# Colour-Sensor.net
KiCad netlist of a schematic drawn in Altium Designer
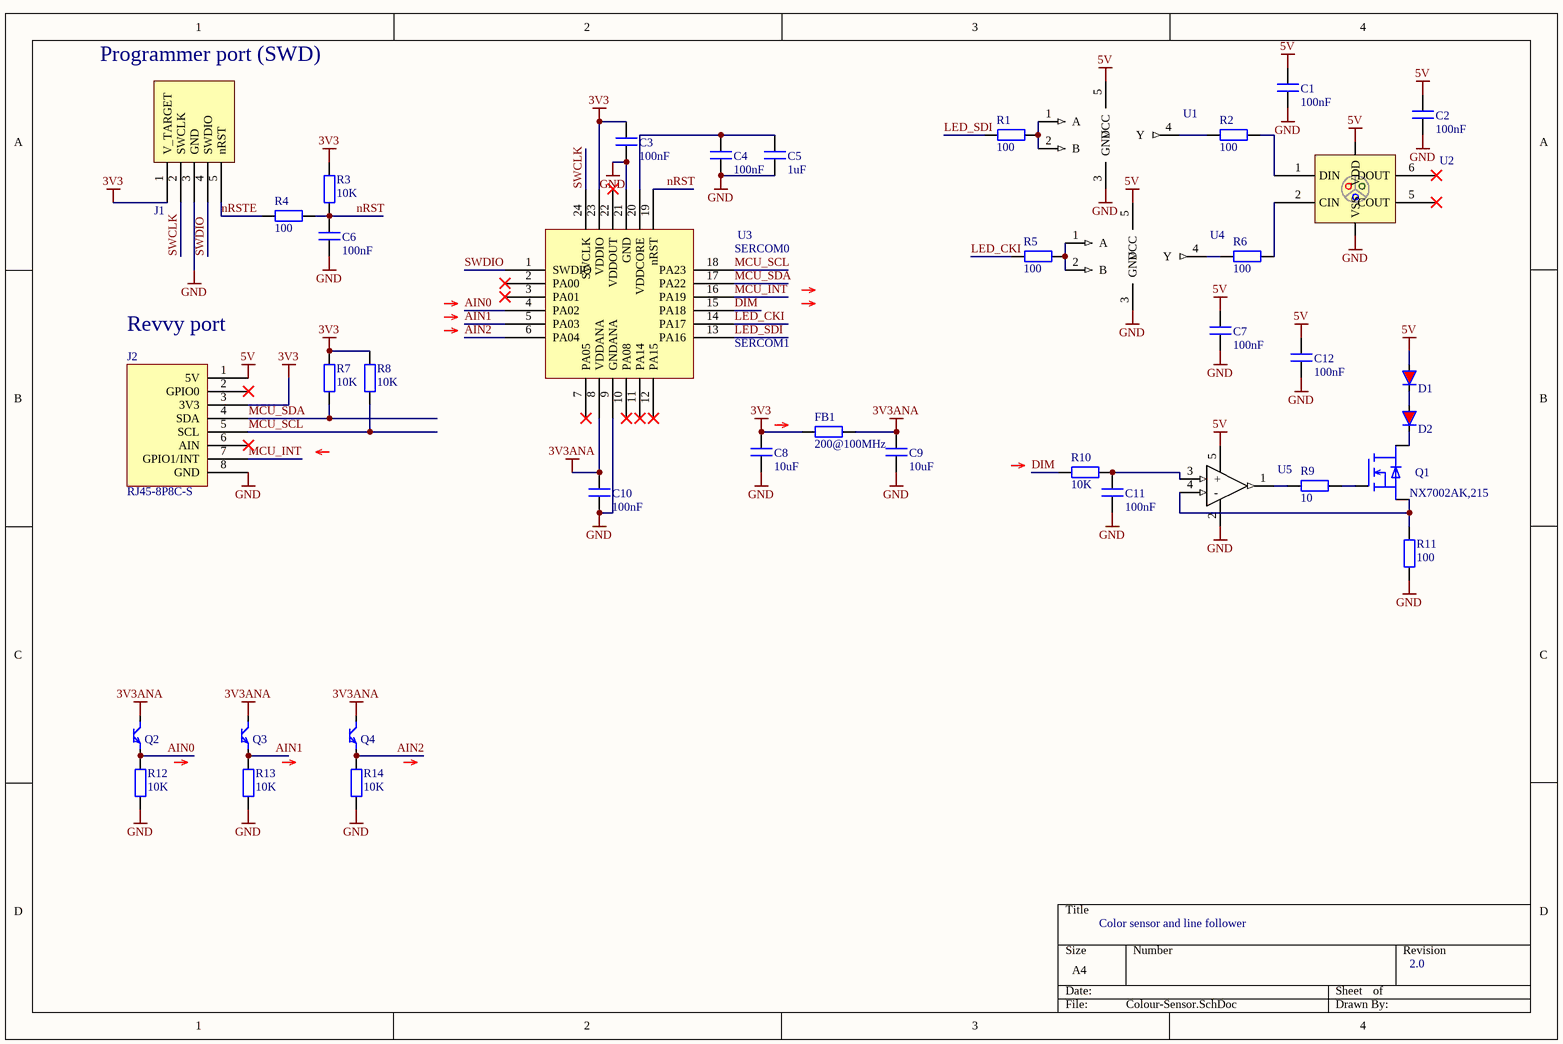
[diagram p0: Colour-Sensor.SchDoc]

(export (version "E")
  (design (tool "Eeschema 10.0.6"))
  (components
    (comp (ref "C1")
      (value "100nF")
      (footprint "CAP1608X06M")
      (libsource (lib "ColorSensor") (part "Capacitor 100n"))
    )
    (comp (ref "C2")
      (value "100nF")
      (footprint "CAP1608X06M")
      (libsource (lib "ColorSensor") (part "Capacitor 100n"))
    )
    (comp (ref "C3")
      (value "100nF")
      (footprint "CAP1608X06M")
      (libsource (lib "ColorSensor") (part "Capacitor 100n"))
    )
    (comp (ref "C4")
      (value "100nF")
      (footprint "CAP1608X06M")
      (libsource (lib "ColorSensor") (part "Capacitor 100n"))
    )
    (comp (ref "C5")
      (value "1uF")
      (footprint "CAP1608X06M")
      (libsource (lib "ColorSensor") (part "Capacitor 1u"))
    )
    (comp (ref "C6")
      (value "100nF")
      (footprint "CAP1608X06M")
      (libsource (lib "ColorSensor") (part "Capacitor 100n"))
    )
    (comp (ref "C7")
      (value "100nF")
      (footprint "CAP1608X06M")
      (libsource (lib "ColorSensor") (part "Capacitor 100n"))
    )
    (comp (ref "C8")
      (value "10uF")
      (footprint "CAP1608X06M")
      (libsource (lib "ColorSensor") (part "Capacitor 10u"))
    )
    (comp (ref "C9")
      (value "10uF")
      (footprint "CAP1608X06M")
      (libsource (lib "ColorSensor") (part "Capacitor 10u"))
    )
    (comp (ref "C10")
      (value "100nF")
      (footprint "CAP1608X06M")
      (libsource (lib "ColorSensor") (part "Capacitor 100n"))
    )
    (comp (ref "C11")
      (value "100nF")
      (footprint "CAP1608X06M")
      (libsource (lib "ColorSensor") (part "Capacitor 100n"))
    )
    (comp (ref "C12")
      (value "100nF")
      (footprint "CAP1608X06M")
      (libsource (lib "ColorSensor") (part "Capacitor 100n"))
    )
    (comp (ref "D1")
      (value "LTST-C190CKT")
      (footprint "SamacSys:LEDC1608X90N")
      (description "LED")
      (fields (field (name "MOUSER2 PART NUMBER") "859-LTST-C190CKT"))
      (libsource (lib "ColorSensor") (part "LTST-C190CKT"))
    )
    (comp (ref "D2")
      (value "LTST-C190CKT")
      (footprint "SamacSys:LEDC1608X90N")
      (description "LED")
      (fields (field (name "MOUSER2 PART NUMBER") "859-LTST-C190CKT"))
      (libsource (lib "ColorSensor") (part "LTST-C190CKT"))
    )
    (comp (ref "FB1")
      (value "200@100MHz")
      (footprint "RESC1608X06M")
      (libsource (lib "ColorSensor") (part "Generic ferrite bead"))
    )
    (comp (ref "J1")
      (value "SWD")
      (footprint "Sullins_GRPB051VWVN-RC")
      (libsource (lib "ColorSensor") (part "SWD"))
    )
    (comp (ref "J2")
      (value "RJ45-8P8C-S")
      (footprint "RJ45-8P8C")
      (libsource (lib "ColorSensor") (part "RJ45-8P8C-S"))
    )
    (comp (ref "Q1")
      (value "NX7002AK,215")
      (footprint "SOT-23-3")
      (fields (field (name "MANUFACTURER") "Nexperia") (field (name "AUTHOR") "ChAl"))
      (libsource (lib "ColorSensor") (part "NX7002AK,215"))
    )
    (comp (ref "Q2")
      (value "KDT00030TR")
      (footprint "SamacSys:KDT00030TR")
      (description "Phototransistor")
      (libsource (lib "ColorSensor") (part "KDT00030TR"))
    )
    (comp (ref "Q3")
      (value "KDT00030TR")
      (footprint "SamacSys:KDT00030TR")
      (description "Phototransistor")
      (libsource (lib "ColorSensor") (part "KDT00030TR"))
    )
    (comp (ref "Q4")
      (value "KDT00030TR")
      (footprint "SamacSys:KDT00030TR")
      (description "Phototransistor")
      (libsource (lib "ColorSensor") (part "KDT00030TR"))
    )
    (comp (ref "R1")
      (value "100")
      (footprint "RESC1608X06M")
      (libsource (lib "ColorSensor") (part "Resistor 100"))
    )
    (comp (ref "R2")
      (value "100")
      (footprint "RESC1608X06M")
      (libsource (lib "ColorSensor") (part "Resistor 100"))
    )
    (comp (ref "R3")
      (value "10K")
      (footprint "RESC1608X06M")
      (libsource (lib "ColorSensor") (part "Resistor 10K"))
    )
    (comp (ref "R4")
      (value "100")
      (footprint "RESC1608X06M")
      (libsource (lib "ColorSensor") (part "Resistor 100"))
    )
    (comp (ref "R5")
      (value "100")
      (footprint "RESC1608X06M")
      (libsource (lib "ColorSensor") (part "Resistor 100"))
    )
    (comp (ref "R6")
      (value "100")
      (footprint "RESC1608X06M")
      (libsource (lib "ColorSensor") (part "Resistor 100"))
    )
    (comp (ref "R7")
      (value "10K")
      (footprint "RESC1608X06M")
      (libsource (lib "ColorSensor") (part "Resistor 10K"))
    )
    (comp (ref "R8")
      (value "10K")
      (footprint "RESC1608X06M")
      (libsource (lib "ColorSensor") (part "Resistor 10K"))
    )
    (comp (ref "R9")
      (value "10")
      (footprint "RESC1608X06M")
      (libsource (lib "ColorSensor") (part "Resistor 10"))
    )
    (comp (ref "R10")
      (value "10K")
      (footprint "RESC1608X06M")
      (libsource (lib "ColorSensor") (part "Resistor 10K"))
    )
    (comp (ref "R11")
      (value "100")
      (footprint "RESC1608X06M")
      (libsource (lib "ColorSensor") (part "Resistor 100"))
    )
    (comp (ref "R12")
      (value "10K")
      (footprint "RESC1608X06M")
      (libsource (lib "ColorSensor") (part "Resistor 10K"))
    )
    (comp (ref "R13")
      (value "10K")
      (footprint "RESC1608X06M")
      (libsource (lib "ColorSensor") (part "Resistor 10K"))
    )
    (comp (ref "R14")
      (value "10K")
      (footprint "RESC1608X06M")
      (libsource (lib "ColorSensor") (part "Resistor 10K"))
    )
    (comp (ref "U1")
      (value "OR gate")
      (footprint "SamacSys:SOT95P270X145-5N")
      (fields (field (name "MANUFACTURER_PART_NUMBER") "SN74LV1T32DCKR"))
      (libsource (lib "ColorSensor") (part "SN74LV1T32"))
    )
    (comp (ref "U2")
      (value "APA102-2020")
      (footprint "APA102")
      (description "RGB LED")
      (libsource (lib "LedMatrix") (part "APA102-2020"))
    )
    (comp (ref "U3")
      (value "ATSAML10D16")
      (footprint "QFN50P400X400X90_HS-25N")
      (description "48MHz 32bit ARM MCU")
      (libsource (lib "ColorSensor") (part "ATSAML10D16"))
    )
    (comp (ref "U4")
      (value "OR gate")
      (footprint "SamacSys:SOT95P270X145-5N")
      (fields (field (name "MANUFACTURER_PART_NUMBER") "SN74LV1T32DCKR"))
      (libsource (lib "ColorSensor") (part "SN74LV1T32"))
    )
    (comp (ref "U5")
      (value "OpAmp")
      (footprint "SamacSys:SOT95P270X145-5N")
      (description "Integrated Circuit")
      (fields
        (field (name "MOUSER2 PART NUMBER") "579-MCP6001T-I/OT")
        (field (name "MANUFACTURER_PART_NUMBER") "MCP6001T-I/OT")
      )
      (libsource (lib "ColorSensor") (part "MCP6001T-I_OT"))
    )
  )
  (nets
    (net (code "1") (name "/AIN0") (class "Default")
      (node (ref "Q2") (pin "2") (pinfunction "E_2") (pintype "passive"))
      (node (ref "R12") (pin "1") (pinfunction "1_1") (pintype "passive"))
      (node (ref "U3") (pin "4") (pinfunction "PA02_4") (pintype "passive"))
    )
    (net (code "2") (name "/AIN1") (class "Default")
      (node (ref "Q3") (pin "2") (pinfunction "E_2") (pintype "passive"))
      (node (ref "R13") (pin "1") (pinfunction "1_1") (pintype "passive"))
      (node (ref "U3") (pin "5") (pinfunction "PA03_5") (pintype "passive"))
    )
    (net (code "3") (name "/AIN2") (class "Default")
      (node (ref "Q4") (pin "2") (pinfunction "E_2") (pintype "passive"))
      (node (ref "R14") (pin "1") (pinfunction "1_1") (pintype "passive"))
      (node (ref "U3") (pin "6") (pinfunction "PA04_6") (pintype "passive"))
    )
    (net (code "4") (name "/DIM") (class "Default")
      (node (ref "R10") (pin "2") (pinfunction "2_2") (pintype "passive"))
      (node (ref "U3") (pin "15") (pinfunction "PA18_15") (pintype "passive"))
    )
    (net (code "5") (name "/LED_CKI") (class "Default")
      (node (ref "R5") (pin "1") (pinfunction "1_1") (pintype "passive"))
      (node (ref "U3") (pin "14") (pinfunction "PA17_14") (pintype "passive"))
    )
    (net (code "6") (name "/LED_SDI") (class "Default")
      (node (ref "R1") (pin "1") (pinfunction "1_1") (pintype "passive"))
      (node (ref "U3") (pin "13") (pinfunction "PA16_13") (pintype "passive"))
    )
    (net (code "7") (name "/MCU_INT") (class "Default")
      (node (ref "J2") (pin "7") (pinfunction "GPIO1/INT_7") (pintype "passive"))
      (node (ref "U3") (pin "16") (pinfunction "PA19_16") (pintype "passive"))
    )
    (net (code "8") (name "/MCU_SCL") (class "Default")
      (node (ref "J2") (pin "5") (pinfunction "SCL_5") (pintype "passive"))
      (node (ref "R8") (pin "1") (pinfunction "1_1") (pintype "passive"))
      (node (ref "U3") (pin "18") (pinfunction "PA23_18") (pintype "passive"))
    )
    (net (code "9") (name "/MCU_SDA") (class "Default")
      (node (ref "J2") (pin "4") (pinfunction "SDA_4") (pintype "passive"))
      (node (ref "R7") (pin "1") (pinfunction "1_1") (pintype "passive"))
      (node (ref "U3") (pin "17") (pinfunction "PA22_17") (pintype "passive"))
    )
    (net (code "10") (name "/SWCLK") (class "Default")
      (node (ref "J1") (pin "2") (pinfunction "SWCLK_2") (pintype "passive"))
      (node (ref "U3") (pin "24") (pinfunction "SWCLK_24") (pintype "passive"))
    )
    (net (code "11") (name "/SWDIO") (class "Default")
      (node (ref "J1") (pin "4") (pinfunction "SWDIO_4") (pintype "passive"))
      (node (ref "U3") (pin "1") (pinfunction "SWDIO_1") (pintype "passive"))
    )
    (net (code "12") (name "/nRST") (class "Default")
      (node (ref "C6") (pin "2") (pinfunction "2_2") (pintype "passive"))
      (node (ref "R3") (pin "1") (pinfunction "1_1") (pintype "passive"))
      (node (ref "R4") (pin "2") (pinfunction "2_2") (pintype "passive"))
      (node (ref "U3") (pin "19") (pinfunction "nRST_19") (pintype "passive"))
    )
    (net (code "13") (name "/nRSTE") (class "Default")
      (node (ref "J1") (pin "5") (pinfunction "nRST_5") (pintype "passive"))
      (node (ref "R4") (pin "1") (pinfunction "1_1") (pintype "passive"))
    )
    (net (code "14") (name "3V3") (class "Default")
      (node (ref "C3") (pin "2") (pinfunction "2_2") (pintype "passive"))
      (node (ref "C8") (pin "2") (pinfunction "2_2") (pintype "passive"))
      (node (ref "FB1") (pin "1") (pinfunction "1_1") (pintype "passive"))
      (node (ref "J1") (pin "1") (pinfunction "V_TARGET_1") (pintype "passive"))
      (node (ref "J2") (pin "3") (pinfunction "3V3_3") (pintype "passive"))
      (node (ref "R3") (pin "2") (pinfunction "2_2") (pintype "passive"))
      (node (ref "R7") (pin "2") (pinfunction "2_2") (pintype "passive"))
      (node (ref "R8") (pin "2") (pinfunction "2_2") (pintype "passive"))
      (node (ref "U3") (pin "23") (pinfunction "VDDIO_23") (pintype "passive"))
    )
    (net (code "15") (name "3V3ANA") (class "Default")
      (node (ref "C10") (pin "2") (pinfunction "2_2") (pintype "passive"))
      (node (ref "C9") (pin "2") (pinfunction "2_2") (pintype "passive"))
      (node (ref "FB1") (pin "2") (pinfunction "2_2") (pintype "passive"))
      (node (ref "Q2") (pin "1") (pinfunction "C_1") (pintype "passive"))
      (node (ref "Q3") (pin "1") (pinfunction "C_1") (pintype "passive"))
      (node (ref "Q4") (pin "1") (pinfunction "C_1") (pintype "passive"))
      (node (ref "U3") (pin "8") (pinfunction "VDDANA_8") (pintype "passive"))
    )
    (net (code "16") (name "5V") (class "Default")
      (node (ref "C1") (pin "2") (pinfunction "2_2") (pintype "passive"))
      (node (ref "C12") (pin "2") (pinfunction "2_2") (pintype "passive"))
      (node (ref "C2") (pin "2") (pinfunction "2_2") (pintype "passive"))
      (node (ref "C7") (pin "2") (pinfunction "2_2") (pintype "passive"))
      (node (ref "D1") (pin "2") (pinfunction "A_2") (pintype "passive"))
      (node (ref "J2") (pin "1") (pinfunction "5V_1") (pintype "passive"))
      (node (ref "U1") (pin "5") (pinfunction "VCC_5") (pintype "power_in"))
      (node (ref "U2") (pin "4") (pinfunction "VDD_4") (pintype "passive"))
      (node (ref "U4") (pin "5") (pinfunction "VCC_5") (pintype "power_in"))
      (node (ref "U5") (pin "5") (pinfunction "VDD_5") (pintype "power_in"))
    )
    (net (code "17") (name "GND") (class "Default")
      (node (ref "C1") (pin "1") (pinfunction "1_1") (pintype "passive"))
      (node (ref "C10") (pin "1") (pinfunction "1_1") (pintype "passive"))
      (node (ref "C11") (pin "1") (pinfunction "1_1") (pintype "passive"))
      (node (ref "C12") (pin "1") (pinfunction "1_1") (pintype "passive"))
      (node (ref "C2") (pin "1") (pinfunction "1_1") (pintype "passive"))
      (node (ref "C3") (pin "1") (pinfunction "1_1") (pintype "passive"))
      (node (ref "C4") (pin "1") (pinfunction "1_1") (pintype "passive"))
      (node (ref "C5") (pin "1") (pinfunction "1_1") (pintype "passive"))
      (node (ref "C6") (pin "1") (pinfunction "1_1") (pintype "passive"))
      (node (ref "C7") (pin "1") (pinfunction "1_1") (pintype "passive"))
      (node (ref "C8") (pin "1") (pinfunction "1_1") (pintype "passive"))
      (node (ref "C9") (pin "1") (pinfunction "1_1") (pintype "passive"))
      (node (ref "J1") (pin "3") (pinfunction "GND_3") (pintype "passive"))
      (node (ref "J2") (pin "8") (pinfunction "GND_8") (pintype "passive"))
      (node (ref "R11") (pin "1") (pinfunction "1_1") (pintype "passive"))
      (node (ref "R12") (pin "2") (pinfunction "2_2") (pintype "passive"))
      (node (ref "R13") (pin "2") (pinfunction "2_2") (pintype "passive"))
      (node (ref "R14") (pin "2") (pinfunction "2_2") (pintype "passive"))
      (node (ref "U1") (pin "3") (pinfunction "GND_3") (pintype "power_in"))
      (node (ref "U2") (pin "3") (pinfunction "VSS_3") (pintype "passive"))
      (node (ref "U3") (pin "21") (pinfunction "GND_21") (pintype "passive"))
      (node (ref "U3") (pin "9") (pinfunction "GNDANA_9") (pintype "passive"))
      (node (ref "U4") (pin "3") (pinfunction "GND_3") (pintype "power_in"))
      (node (ref "U5") (pin "2") (pinfunction "VSS_2") (pintype "power_in"))
    )
    (net (code "18") (name "Net-(D1-K)") (class "Default")
      (node (ref "D1") (pin "1") (pinfunction "K_1") (pintype "passive"))
      (node (ref "D2") (pin "2") (pinfunction "A_2") (pintype "passive"))
    )
    (net (code "19") (name "Net-(D2-K)") (class "Default")
      (node (ref "D2") (pin "1") (pinfunction "K_1") (pintype "passive"))
      (node (ref "Q1") (pin "3") (pinfunction "D_3") (pintype "passive"))
    )
    (net (code "20") (name "Net-(Q1-G)") (class "Default")
      (node (ref "Q1") (pin "1") (pinfunction "G_1") (pintype "passive"))
      (node (ref "R9") (pin "2") (pinfunction "2_2") (pintype "passive"))
    )
    (net (code "21") (name "Net-(Q1-S)") (class "Default")
      (node (ref "Q1") (pin "2") (pinfunction "S_2") (pintype "passive"))
      (node (ref "R11") (pin "2") (pinfunction "2_2") (pintype "passive"))
      (node (ref "U5") (pin "4") (pinfunction "-_4") (pintype "input"))
    )
    (net (code "22") (name "Net-(U1-A)") (class "Default")
      (node (ref "R1") (pin "2") (pinfunction "2_2") (pintype "passive"))
      (node (ref "U1") (pin "1") (pinfunction "A_1") (pintype "input"))
      (node (ref "U1") (pin "2") (pinfunction "B_2") (pintype "input"))
    )
    (net (code "23") (name "Net-(U1-Y)") (class "Default")
      (node (ref "R2") (pin "1") (pinfunction "1_1") (pintype "passive"))
      (node (ref "U1") (pin "4") (pinfunction "Y_4") (pintype "output"))
    )
    (net (code "24") (name "Net-(U2-CIN)") (class "Default")
      (node (ref "R6") (pin "2") (pinfunction "2_2") (pintype "passive"))
      (node (ref "U2") (pin "2") (pinfunction "CIN_2") (pintype "passive"))
    )
    (net (code "25") (name "Net-(U2-DIN)") (class "Default")
      (node (ref "R2") (pin "2") (pinfunction "2_2") (pintype "passive"))
      (node (ref "U2") (pin "1") (pinfunction "DIN_1") (pintype "passive"))
    )
    (net (code "26") (name "Net-(U3-VDDCORE)") (class "Default")
      (node (ref "C4") (pin "2") (pinfunction "2_2") (pintype "passive"))
      (node (ref "C5") (pin "2") (pinfunction "2_2") (pintype "passive"))
      (node (ref "U3") (pin "20") (pinfunction "VDDCORE_20") (pintype "passive"))
    )
    (net (code "27") (name "Net-(U4-A)") (class "Default")
      (node (ref "R5") (pin "2") (pinfunction "2_2") (pintype "passive"))
      (node (ref "U4") (pin "1") (pinfunction "A_1") (pintype "input"))
      (node (ref "U4") (pin "2") (pinfunction "B_2") (pintype "input"))
    )
    (net (code "28") (name "Net-(U4-Y)") (class "Default")
      (node (ref "R6") (pin "1") (pinfunction "1_1") (pintype "passive"))
      (node (ref "U4") (pin "4") (pinfunction "Y_4") (pintype "output"))
    )
    (net (code "29") (name "Net-(U5-+)") (class "Default")
      (node (ref "C11") (pin "2") (pinfunction "2_2") (pintype "passive"))
      (node (ref "R10") (pin "1") (pinfunction "1_1") (pintype "passive"))
      (node (ref "U5") (pin "3") (pinfunction "+_3") (pintype "input"))
    )
    (net (code "30") (name "Net-(U5-VOUT)") (class "Default")
      (node (ref "R9") (pin "1") (pinfunction "1_1") (pintype "passive"))
      (node (ref "U5") (pin "1") (pinfunction "VOUT_1") (pintype "output"))
    )
    (net (code "31") (name "unconnected-(J2-AIN-Pad6)") (class "Default")
      (node (ref "J2") (pin "6") (pinfunction "AIN_6") (pintype "passive+no_connect"))
    )
    (net (code "32") (name "unconnected-(J2-GPIO0-Pad2)") (class "Default")
      (node (ref "J2") (pin "2") (pinfunction "GPIO0_2") (pintype "passive+no_connect"))
    )
    (net (code "33") (name "unconnected-(U2-COUT-Pad5)") (class "Default")
      (node (ref "U2") (pin "5") (pinfunction "COUT_5") (pintype "passive+no_connect"))
    )
    (net (code "34") (name "unconnected-(U2-DOUT-Pad6)") (class "Default")
      (node (ref "U2") (pin "6") (pinfunction "DOUT_6") (pintype "passive+no_connect"))
    )
    (net (code "35") (name "unconnected-(U3-PA00-Pad2)") (class "Default")
      (node (ref "U3") (pin "2") (pinfunction "PA00_2") (pintype "passive+no_connect"))
    )
    (net (code "36") (name "unconnected-(U3-PA01-Pad3)") (class "Default")
      (node (ref "U3") (pin "3") (pinfunction "PA01_3") (pintype "passive+no_connect"))
    )
    (net (code "37") (name "unconnected-(U3-PA05-Pad7)") (class "Default")
      (node (ref "U3") (pin "7") (pinfunction "PA05_7") (pintype "passive+no_connect"))
    )
    (net (code "38") (name "unconnected-(U3-PA08-Pad10)") (class "Default")
      (node (ref "U3") (pin "10") (pinfunction "PA08_10") (pintype "passive+no_connect"))
    )
    (net (code "39") (name "unconnected-(U3-PA14-Pad11)") (class "Default")
      (node (ref "U3") (pin "11") (pinfunction "PA14_11") (pintype "passive+no_connect"))
    )
    (net (code "40") (name "unconnected-(U3-PA15-Pad12)") (class "Default")
      (node (ref "U3") (pin "12") (pinfunction "PA15_12") (pintype "passive+no_connect"))
    )
    (net (code "41") (name "unconnected-(U3-VDDOUT-Pad22)") (class "Default")
      (node (ref "U3") (pin "22") (pinfunction "VDDOUT_22") (pintype "passive+no_connect"))
    )
  )
)
